# TeensySonarBoard.net
KiCad netlist of a schematic drawn in EAGLE
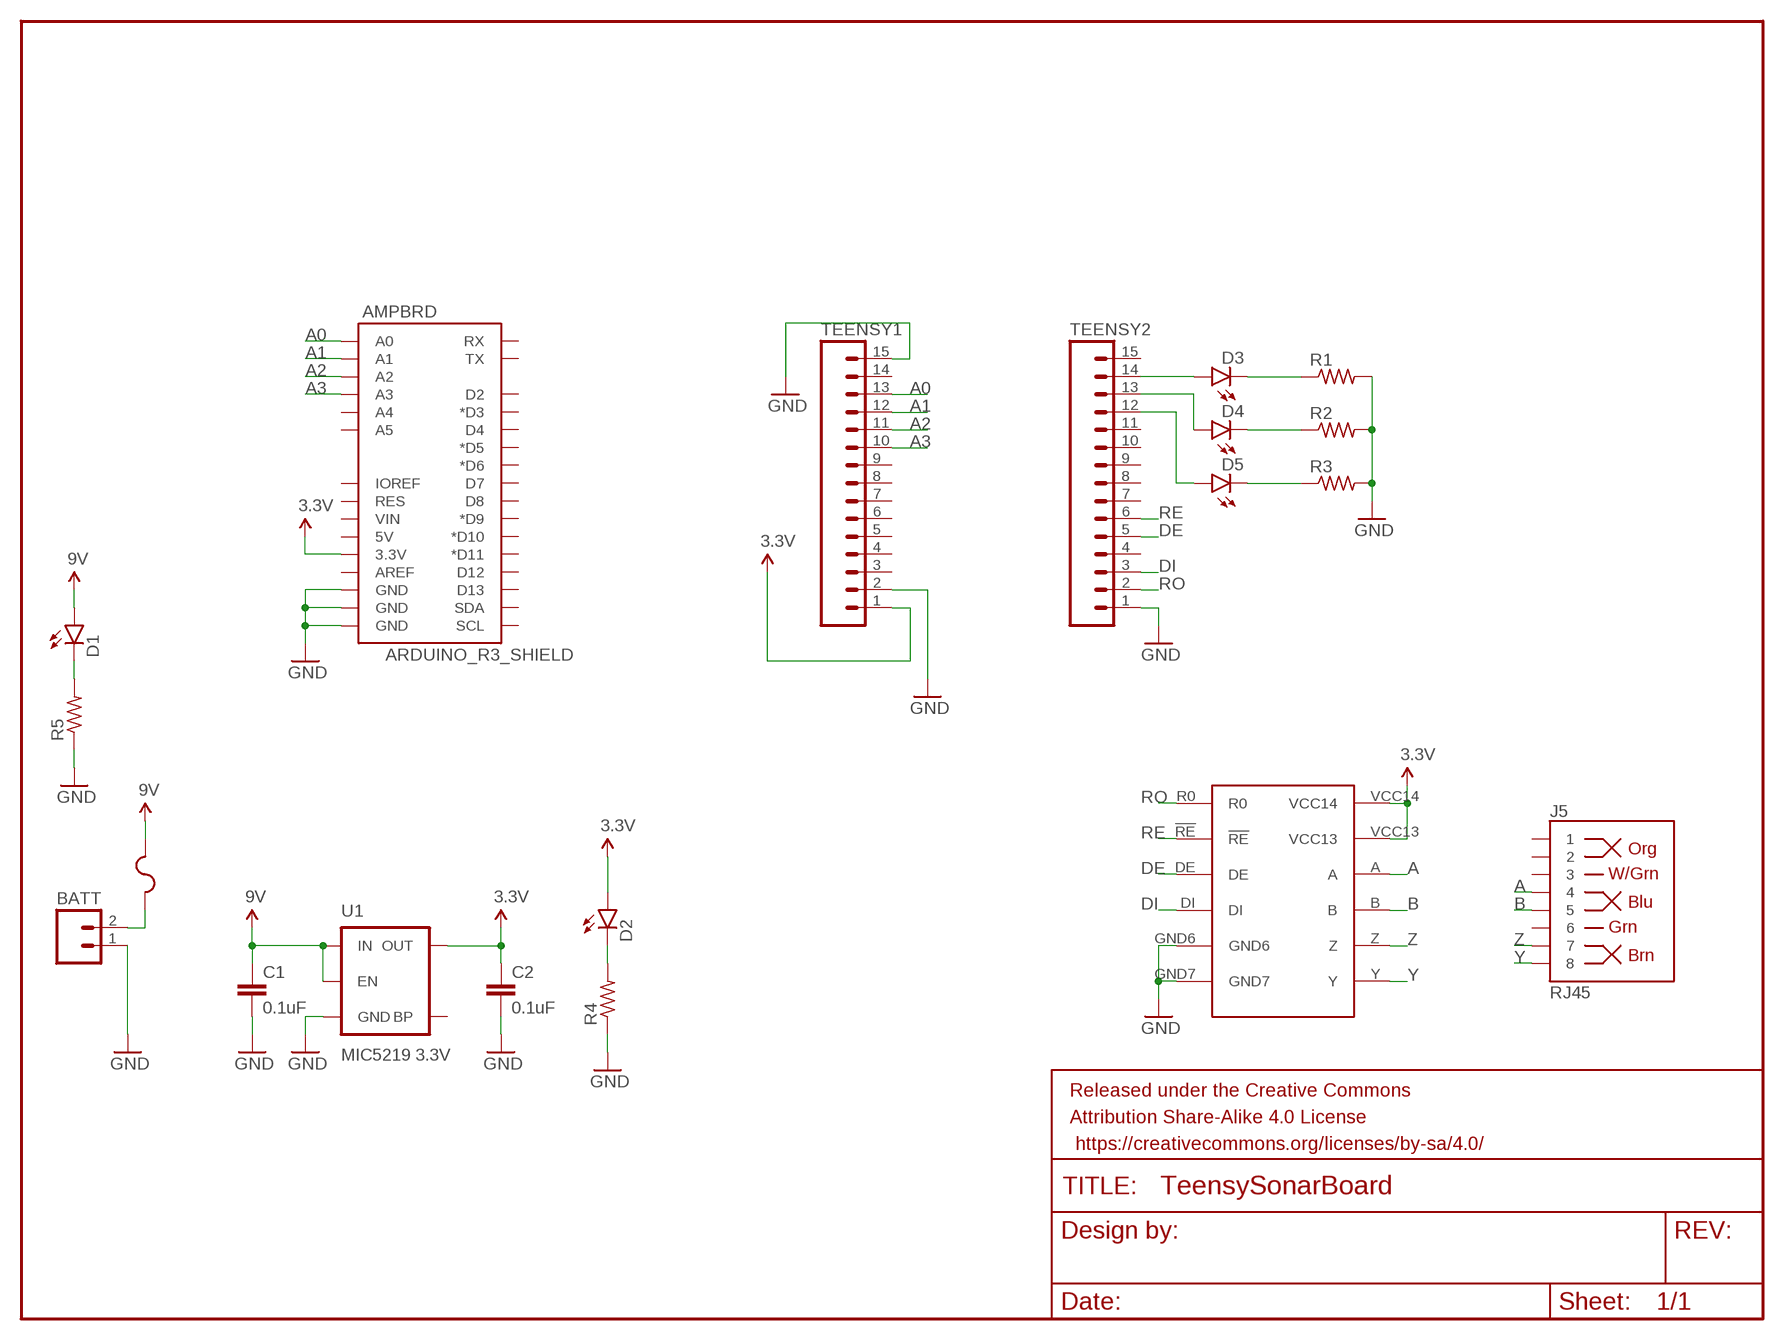
[diagram p0: schematic, sheet 1]

(export (version "E")
  (design (tool "Eeschema 10.0.6"))
  (components
    (comp (ref "AMPBRD")
      (value "ARDUINO_R3_SHIELD")
      (footprint "eagle-import:UNO_R3_SHIELD")
      (libsource (lib "eagle-import") (part "ARDUINO_R3_SHIELD"))
    )
    (comp (ref "BATT")
      (value "M02JST-PTH-VERT")
      (footprint "eagle-import:JST-2-PTH-VERT")
      (libsource (lib "eagle-import") (part "M02JST-PTH-VERT"))
    )
    (comp (ref "C1")
      (value "0.1uF")
      (footprint "eagle-import:0603-CAP")
      (libsource (lib "eagle-import") (part "CAP0603-CAP"))
    )
    (comp (ref "C2")
      (value "0.1uF")
      (footprint "eagle-import:0603-CAP")
      (libsource (lib "eagle-import") (part "CAP0603-CAP"))
    )
    (comp (ref "D1")
      (value "LED0603")
      (footprint "eagle-import:LED-0603")
      (libsource (lib "eagle-import") (part "LED0603"))
    )
    (comp (ref "D2")
      (value "LED0603")
      (footprint "eagle-import:LED-0603")
      (libsource (lib "eagle-import") (part "LED0603"))
    )
    (comp (ref "D3")
      (value "LED0603")
      (footprint "eagle-import:LED-0603")
      (libsource (lib "eagle-import") (part "LED0603"))
    )
    (comp (ref "D4")
      (value "LED0603")
      (footprint "eagle-import:LED-0603")
      (libsource (lib "eagle-import") (part "LED0603"))
    )
    (comp (ref "D5")
      (value "LED0603")
      (footprint "eagle-import:LED-0603")
      (libsource (lib "eagle-import") (part "LED0603"))
    )
    (comp (ref "F1")
      (value "2A")
      (footprint "eagle-import:KEYSTONE_FUSE_3587")
      (libsource (lib "eagle-import") (part "KEYSTONE_FUSE_3587"))
    )
    (comp (ref "FRAME1")
      (value "FRAME-LETTERNO_PACKAGE")
      (footprint "eagle-import:DUMMY")
      (fields (field (name "DESIGNER") "Nobody"))
      (libsource (lib "eagle-import") (part "FRAME-LETTERNO_PACKAGE"))
    )
    (comp (ref "J5")
      (value "RJ45")
      (footprint "eagle-import:RJ45-8")
      (libsource (lib "eagle-import") (part "RJ45-8PTH"))
    )
    (comp (ref "R1")
      (value "R-US_R0603")
      (footprint "eagle-import:R0603")
      (libsource (lib "eagle-import") (part "R-US_R0603"))
    )
    (comp (ref "R2")
      (value "R-US_R0603")
      (footprint "eagle-import:R0603")
      (libsource (lib "eagle-import") (part "R-US_R0603"))
    )
    (comp (ref "R3")
      (value "R-US_R0603")
      (footprint "eagle-import:R0603")
      (libsource (lib "eagle-import") (part "R-US_R0603"))
    )
    (comp (ref "R4")
      (value "R-US_R0603")
      (footprint "eagle-import:R0603")
      (libsource (lib "eagle-import") (part "R-US_R0603"))
    )
    (comp (ref "R5")
      (value "R-US_R0603")
      (footprint "eagle-import:R0603")
      (libsource (lib "eagle-import") (part "R-US_R0603"))
    )
    (comp (ref "TEENSY1")
      (value "M15")
      (footprint "eagle-import:1X15")
      (libsource (lib "eagle-import") (part "M15"))
    )
    (comp (ref "TEENSY2")
      (value "M15")
      (footprint "eagle-import:1X15")
      (libsource (lib "eagle-import") (part "M15"))
    )
    (comp (ref "U$1")
      (value "MAX3491")
      (footprint "eagle-import:MAX3491")
      (libsource (lib "eagle-import") (part "MAX3491"))
    )
    (comp (ref "U1")
      (value "MIC5219 3.3V")
      (footprint "eagle-import:SOT23-5")
      (libsource (lib "eagle-import") (part "V_REG_MIC52193.3V"))
    )
  )
  (nets
    (net (code "1") (name "/A") (class "Default")
      (node (ref "J5") (pin "4") (pinfunction "4_4") (pintype "bidirectional"))
      (node (ref "U$1") (pin "A") (pinfunction "A_A") (pintype "bidirectional"))
    )
    (net (code "2") (name "/A0") (class "Default")
      (node (ref "AMPBRD") (pin "A0") (pinfunction "A0_A0") (pintype "bidirectional"))
      (node (ref "TEENSY1") (pin "13") (pinfunction "13_13") (pintype "passive"))
    )
    (net (code "3") (name "/A1") (class "Default")
      (node (ref "AMPBRD") (pin "A1") (pinfunction "A1_A1") (pintype "bidirectional"))
      (node (ref "TEENSY1") (pin "12") (pinfunction "12_12") (pintype "passive"))
    )
    (net (code "4") (name "/A2") (class "Default")
      (node (ref "AMPBRD") (pin "A2") (pinfunction "A2_A2") (pintype "bidirectional"))
      (node (ref "TEENSY1") (pin "11") (pinfunction "11_11") (pintype "passive"))
    )
    (net (code "5") (name "/A3") (class "Default")
      (node (ref "AMPBRD") (pin "A3") (pinfunction "A3_A3") (pintype "bidirectional"))
      (node (ref "TEENSY1") (pin "10") (pinfunction "10_10") (pintype "passive"))
    )
    (net (code "6") (name "/B") (class "Default")
      (node (ref "J5") (pin "5") (pinfunction "5_5") (pintype "bidirectional"))
      (node (ref "U$1") (pin "B") (pinfunction "B_B") (pintype "bidirectional"))
    )
    (net (code "7") (name "/DE") (class "Default")
      (node (ref "TEENSY2") (pin "5") (pinfunction "5_5") (pintype "passive"))
      (node (ref "U$1") (pin "DE") (pinfunction "DE_DE") (pintype "bidirectional"))
    )
    (net (code "8") (name "/DI") (class "Default")
      (node (ref "TEENSY2") (pin "3") (pinfunction "3_3") (pintype "passive"))
      (node (ref "U$1") (pin "DI") (pinfunction "DI_DI") (pintype "bidirectional"))
    )
    (net (code "9") (name "/RE") (class "Default")
      (node (ref "TEENSY2") (pin "6") (pinfunction "6_6") (pintype "passive"))
      (node (ref "U$1") (pin "!RE") (pinfunction "~{RE}_!RE") (pintype "bidirectional"))
    )
    (net (code "10") (name "/RO") (class "Default")
      (node (ref "TEENSY2") (pin "2") (pinfunction "2_2") (pintype "passive"))
      (node (ref "U$1") (pin "R0") (pinfunction "R0_R0") (pintype "bidirectional"))
    )
    (net (code "11") (name "/Y") (class "Default")
      (node (ref "J5") (pin "8") (pinfunction "8_8") (pintype "bidirectional"))
      (node (ref "U$1") (pin "Y") (pinfunction "Y_Y") (pintype "bidirectional"))
    )
    (net (code "12") (name "/Z") (class "Default")
      (node (ref "J5") (pin "7") (pinfunction "7_7") (pintype "bidirectional"))
      (node (ref "U$1") (pin "Z") (pinfunction "Z_Z") (pintype "bidirectional"))
    )
    (net (code "13") (name "3.3V") (class "Default")
      (node (ref "AMPBRD") (pin "3.3V") (pinfunction "3.3V_3.3V") (pintype "bidirectional"))
      (node (ref "C2") (pin "1") (pinfunction "1_1") (pintype "passive"))
      (node (ref "D2") (pin "A") (pinfunction "A_A") (pintype "passive"))
      (node (ref "TEENSY1") (pin "1") (pinfunction "1_1") (pintype "passive"))
      (node (ref "U$1") (pin "VCC13") (pinfunction "VCC13_VCC13") (pintype "bidirectional"))
      (node (ref "U$1") (pin "VCC14") (pinfunction "VCC14_VCC14") (pintype "bidirectional"))
      (node (ref "U1") (pin "5") (pinfunction "OUT_5") (pintype "passive"))
    )
    (net (code "14") (name "9V") (class "Default")
      (node (ref "C1") (pin "1") (pinfunction "1_1") (pintype "passive"))
      (node (ref "D1") (pin "A") (pinfunction "A_A") (pintype "passive"))
      (node (ref "F1") (pin "P$3") (pinfunction "P$2_P$3") (pintype "bidirectional"))
      (node (ref "F1") (pin "P$4") (pinfunction "P$2_P$4") (pintype "bidirectional"))
      (node (ref "U1") (pin "1") (pinfunction "IN_1") (pintype "input"))
      (node (ref "U1") (pin "3") (pinfunction "EN_3") (pintype "input"))
    )
    (net (code "15") (name "GND") (class "Default")
      (node (ref "AMPBRD") (pin "GND@0") (pinfunction "GND_GND@0") (pintype "bidirectional"))
      (node (ref "AMPBRD") (pin "GND@1") (pinfunction "GND_GND@1") (pintype "bidirectional"))
      (node (ref "AMPBRD") (pin "GND@2") (pinfunction "GND_GND@2") (pintype "bidirectional"))
      (node (ref "BATT") (pin "1") (pinfunction "1_1") (pintype "passive"))
      (node (ref "C1") (pin "2") (pinfunction "2_2") (pintype "passive"))
      (node (ref "C2") (pin "2") (pinfunction "2_2") (pintype "passive"))
      (node (ref "R1") (pin "2") (pinfunction "2_2") (pintype "passive"))
      (node (ref "R2") (pin "2") (pinfunction "2_2") (pintype "passive"))
      (node (ref "R3") (pin "2") (pinfunction "2_2") (pintype "passive"))
      (node (ref "R4") (pin "1") (pinfunction "1_1") (pintype "passive"))
      (node (ref "R5") (pin "1") (pinfunction "1_1") (pintype "passive"))
      (node (ref "TEENSY1") (pin "15") (pinfunction "15_15") (pintype "passive"))
      (node (ref "TEENSY1") (pin "2") (pinfunction "2_2") (pintype "passive"))
      (node (ref "TEENSY2") (pin "1") (pinfunction "1_1") (pintype "passive"))
      (node (ref "U$1") (pin "GND6") (pinfunction "GND6_GND6") (pintype "bidirectional"))
      (node (ref "U$1") (pin "GND7") (pinfunction "GND7_GND7") (pintype "bidirectional"))
      (node (ref "U1") (pin "2") (pinfunction "GND_2") (pintype "input"))
    )
    (net (code "16") (name "Net-(BATT-Pad2)") (class "Default")
      (node (ref "BATT") (pin "2") (pinfunction "2_2") (pintype "passive"))
      (node (ref "F1") (pin "P$1") (pinfunction "P$1_P$1") (pintype "bidirectional"))
      (node (ref "F1") (pin "P$2") (pinfunction "P$1_P$2") (pintype "bidirectional"))
    )
    (net (code "17") (name "Net-(D1-PadC)") (class "Default")
      (node (ref "D1") (pin "C") (pinfunction "C_C") (pintype "passive"))
      (node (ref "R5") (pin "2") (pinfunction "2_2") (pintype "passive"))
    )
    (net (code "18") (name "Net-(D2-PadC)") (class "Default")
      (node (ref "D2") (pin "C") (pinfunction "C_C") (pintype "passive"))
      (node (ref "R4") (pin "2") (pinfunction "2_2") (pintype "passive"))
    )
    (net (code "19") (name "Net-(D3-PadA)") (class "Default")
      (node (ref "D3") (pin "A") (pinfunction "A_A") (pintype "passive"))
      (node (ref "TEENSY2") (pin "14") (pinfunction "14_14") (pintype "passive"))
    )
    (net (code "20") (name "Net-(D3-PadC)") (class "Default")
      (node (ref "D3") (pin "C") (pinfunction "C_C") (pintype "passive"))
      (node (ref "R1") (pin "1") (pinfunction "1_1") (pintype "passive"))
    )
    (net (code "21") (name "Net-(D4-PadA)") (class "Default")
      (node (ref "D4") (pin "A") (pinfunction "A_A") (pintype "passive"))
      (node (ref "TEENSY2") (pin "13") (pinfunction "13_13") (pintype "passive"))
    )
    (net (code "22") (name "Net-(D4-PadC)") (class "Default")
      (node (ref "D4") (pin "C") (pinfunction "C_C") (pintype "passive"))
      (node (ref "R2") (pin "1") (pinfunction "1_1") (pintype "passive"))
    )
    (net (code "23") (name "Net-(D5-PadA)") (class "Default")
      (node (ref "D5") (pin "A") (pinfunction "A_A") (pintype "passive"))
      (node (ref "TEENSY2") (pin "12") (pinfunction "12_12") (pintype "passive"))
    )
    (net (code "24") (name "Net-(D5-PadC)") (class "Default")
      (node (ref "D5") (pin "C") (pinfunction "C_C") (pintype "passive"))
      (node (ref "R3") (pin "1") (pinfunction "1_1") (pintype "passive"))
    )
    (net (code "25") (name "unconnected-(AMPBRD-*D3-PadD3)") (class "Default")
      (node (ref "AMPBRD") (pin "D3") (pinfunction "*D3_D3") (pintype "bidirectional"))
    )
    (net (code "26") (name "unconnected-(AMPBRD-*D5-PadD5)") (class "Default")
      (node (ref "AMPBRD") (pin "D5") (pinfunction "*D5_D5") (pintype "bidirectional"))
    )
    (net (code "27") (name "unconnected-(AMPBRD-*D6-PadD6)") (class "Default")
      (node (ref "AMPBRD") (pin "D6") (pinfunction "*D6_D6") (pintype "bidirectional"))
    )
    (net (code "28") (name "unconnected-(AMPBRD-*D9-PadD9)") (class "Default")
      (node (ref "AMPBRD") (pin "D9") (pinfunction "*D9_D9") (pintype "bidirectional"))
    )
    (net (code "29") (name "unconnected-(AMPBRD-*D10-PadD10)") (class "Default")
      (node (ref "AMPBRD") (pin "D10") (pinfunction "*D10_D10") (pintype "bidirectional"))
    )
    (net (code "30") (name "unconnected-(AMPBRD-*D11-PadD11)") (class "Default")
      (node (ref "AMPBRD") (pin "D11") (pinfunction "*D11_D11") (pintype "bidirectional"))
    )
    (net (code "31") (name "unconnected-(AMPBRD-Pad5V)") (class "Default")
      (node (ref "AMPBRD") (pin "5V") (pinfunction "5V_5V") (pintype "bidirectional"))
    )
    (net (code "32") (name "unconnected-(AMPBRD-PadA4)") (class "Default")
      (node (ref "AMPBRD") (pin "A4") (pinfunction "A4_A4") (pintype "bidirectional"))
    )
    (net (code "33") (name "unconnected-(AMPBRD-PadA5)") (class "Default")
      (node (ref "AMPBRD") (pin "A5") (pinfunction "A5_A5") (pintype "bidirectional"))
    )
    (net (code "34") (name "unconnected-(AMPBRD-PadAREF)") (class "Default")
      (node (ref "AMPBRD") (pin "AREF") (pinfunction "AREF_AREF") (pintype "bidirectional"))
    )
    (net (code "35") (name "unconnected-(AMPBRD-PadD2)") (class "Default")
      (node (ref "AMPBRD") (pin "D2") (pinfunction "D2_D2") (pintype "bidirectional"))
    )
    (net (code "36") (name "unconnected-(AMPBRD-PadD4)") (class "Default")
      (node (ref "AMPBRD") (pin "D4") (pinfunction "D4_D4") (pintype "bidirectional"))
    )
    (net (code "37") (name "unconnected-(AMPBRD-PadD7)") (class "Default")
      (node (ref "AMPBRD") (pin "D7") (pinfunction "D7_D7") (pintype "bidirectional"))
    )
    (net (code "38") (name "unconnected-(AMPBRD-PadD8)") (class "Default")
      (node (ref "AMPBRD") (pin "D8") (pinfunction "D8_D8") (pintype "bidirectional"))
    )
    (net (code "39") (name "unconnected-(AMPBRD-PadD12)") (class "Default")
      (node (ref "AMPBRD") (pin "D12") (pinfunction "D12_D12") (pintype "bidirectional"))
    )
    (net (code "40") (name "unconnected-(AMPBRD-PadD13)") (class "Default")
      (node (ref "AMPBRD") (pin "D13") (pinfunction "D13_D13") (pintype "bidirectional"))
    )
    (net (code "41") (name "unconnected-(AMPBRD-PadIOREF)") (class "Default")
      (node (ref "AMPBRD") (pin "IOREF") (pinfunction "IOREF_IOREF") (pintype "bidirectional"))
    )
    (net (code "42") (name "unconnected-(AMPBRD-PadRES)") (class "Default")
      (node (ref "AMPBRD") (pin "RES") (pinfunction "RES_RES") (pintype "bidirectional"))
    )
    (net (code "43") (name "unconnected-(AMPBRD-PadRX)") (class "Default")
      (node (ref "AMPBRD") (pin "RX") (pinfunction "RX_RX") (pintype "bidirectional"))
    )
    (net (code "44") (name "unconnected-(AMPBRD-PadSCL)") (class "Default")
      (node (ref "AMPBRD") (pin "SCL") (pinfunction "SCL_SCL") (pintype "bidirectional"))
    )
    (net (code "45") (name "unconnected-(AMPBRD-PadSDA)") (class "Default")
      (node (ref "AMPBRD") (pin "SDA") (pinfunction "SDA_SDA") (pintype "bidirectional"))
    )
    (net (code "46") (name "unconnected-(AMPBRD-PadTX)") (class "Default")
      (node (ref "AMPBRD") (pin "TX") (pinfunction "TX_TX") (pintype "bidirectional"))
    )
    (net (code "47") (name "unconnected-(AMPBRD-PadVIN)") (class "Default")
      (node (ref "AMPBRD") (pin "VIN") (pinfunction "VIN_VIN") (pintype "bidirectional"))
    )
    (net (code "48") (name "unconnected-(J5-Pad1)") (class "Default")
      (node (ref "J5") (pin "1") (pinfunction "1_1") (pintype "bidirectional"))
    )
    (net (code "49") (name "unconnected-(J5-Pad2)") (class "Default")
      (node (ref "J5") (pin "2") (pinfunction "2_2") (pintype "bidirectional"))
    )
    (net (code "50") (name "unconnected-(J5-Pad3)") (class "Default")
      (node (ref "J5") (pin "3") (pinfunction "3_3") (pintype "bidirectional"))
    )
    (net (code "51") (name "unconnected-(J5-Pad6)") (class "Default")
      (node (ref "J5") (pin "6") (pinfunction "6_6") (pintype "bidirectional"))
    )
    (net (code "52") (name "unconnected-(TEENSY1-Pad3)") (class "Default")
      (node (ref "TEENSY1") (pin "3") (pinfunction "3_3") (pintype "passive"))
    )
    (net (code "53") (name "unconnected-(TEENSY1-Pad4)") (class "Default")
      (node (ref "TEENSY1") (pin "4") (pinfunction "4_4") (pintype "passive"))
    )
    (net (code "54") (name "unconnected-(TEENSY1-Pad5)") (class "Default")
      (node (ref "TEENSY1") (pin "5") (pinfunction "5_5") (pintype "passive"))
    )
    (net (code "55") (name "unconnected-(TEENSY1-Pad6)") (class "Default")
      (node (ref "TEENSY1") (pin "6") (pinfunction "6_6") (pintype "passive"))
    )
    (net (code "56") (name "unconnected-(TEENSY1-Pad7)") (class "Default")
      (node (ref "TEENSY1") (pin "7") (pinfunction "7_7") (pintype "passive"))
    )
    (net (code "57") (name "unconnected-(TEENSY1-Pad8)") (class "Default")
      (node (ref "TEENSY1") (pin "8") (pinfunction "8_8") (pintype "passive"))
    )
    (net (code "58") (name "unconnected-(TEENSY1-Pad9)") (class "Default")
      (node (ref "TEENSY1") (pin "9") (pinfunction "9_9") (pintype "passive"))
    )
    (net (code "59") (name "unconnected-(TEENSY1-Pad14)") (class "Default")
      (node (ref "TEENSY1") (pin "14") (pinfunction "14_14") (pintype "passive"))
    )
    (net (code "60") (name "unconnected-(TEENSY2-Pad4)") (class "Default")
      (node (ref "TEENSY2") (pin "4") (pinfunction "4_4") (pintype "passive"))
    )
    (net (code "61") (name "unconnected-(TEENSY2-Pad7)") (class "Default")
      (node (ref "TEENSY2") (pin "7") (pinfunction "7_7") (pintype "passive"))
    )
    (net (code "62") (name "unconnected-(TEENSY2-Pad8)") (class "Default")
      (node (ref "TEENSY2") (pin "8") (pinfunction "8_8") (pintype "passive"))
    )
    (net (code "63") (name "unconnected-(TEENSY2-Pad9)") (class "Default")
      (node (ref "TEENSY2") (pin "9") (pinfunction "9_9") (pintype "passive"))
    )
    (net (code "64") (name "unconnected-(TEENSY2-Pad10)") (class "Default")
      (node (ref "TEENSY2") (pin "10") (pinfunction "10_10") (pintype "passive"))
    )
    (net (code "65") (name "unconnected-(TEENSY2-Pad11)") (class "Default")
      (node (ref "TEENSY2") (pin "11") (pinfunction "11_11") (pintype "passive"))
    )
    (net (code "66") (name "unconnected-(TEENSY2-Pad15)") (class "Default")
      (node (ref "TEENSY2") (pin "15") (pinfunction "15_15") (pintype "passive"))
    )
    (net (code "67") (name "unconnected-(U1-BP-Pad4)") (class "Default")
      (node (ref "U1") (pin "4") (pinfunction "BP_4") (pintype "input"))
    )
  )
)
